# telfer-control.net
KiCad netlist of a schematic drawn in EAGLE
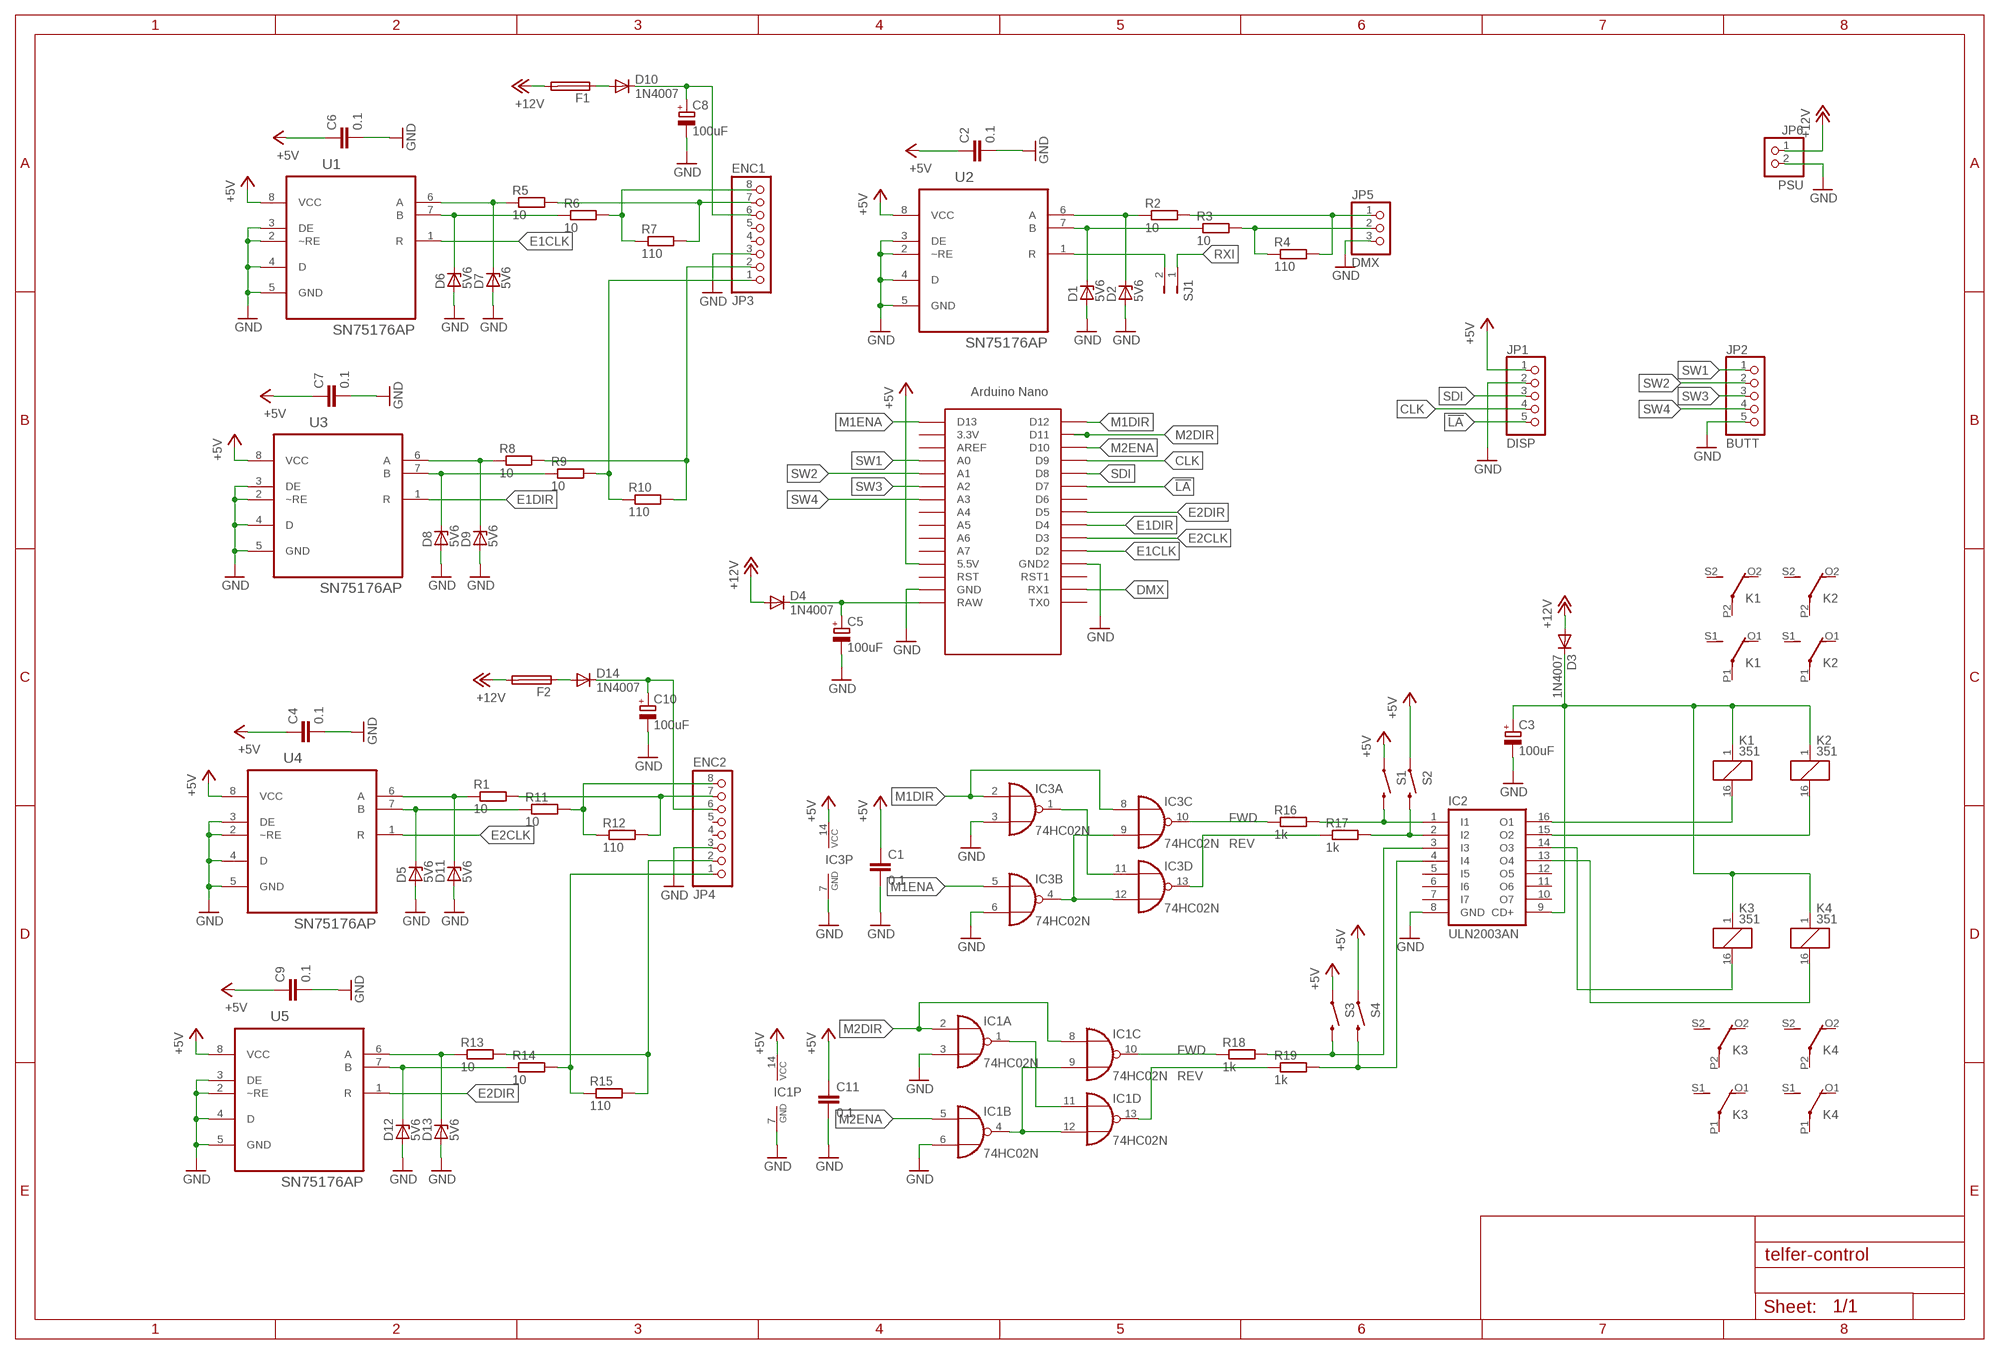
[diagram p0: schematic, sheet 1]

(export (version "E")
  (design (tool "Eeschema 10.0.6"))
  (components
    (comp (ref "C1")
      (value "0.1")
      (footprint "eagle-import:C050-025X075")
      (libsource (lib "eagle-import") (part "C-EU050-025X075"))
    )
    (comp (ref "C2")
      (value "0.1")
      (footprint "eagle-import:C050-025X075")
      (libsource (lib "eagle-import") (part "C-EU050-025X075"))
    )
    (comp (ref "C3")
      (value "100uF")
      (footprint "eagle-import:E2,5-7")
      (libsource (lib "eagle-import") (part "CPOL-EUE2.5-7"))
    )
    (comp (ref "C4")
      (value "0.1")
      (footprint "eagle-import:C050-025X075")
      (libsource (lib "eagle-import") (part "C-EU050-025X075"))
    )
    (comp (ref "C5")
      (value "100uF")
      (footprint "eagle-import:E2,5-7")
      (libsource (lib "eagle-import") (part "CPOL-EUE2.5-7"))
    )
    (comp (ref "C6")
      (value "0.1")
      (footprint "eagle-import:C050-025X075")
      (libsource (lib "eagle-import") (part "C-EU050-025X075"))
    )
    (comp (ref "C7")
      (value "0.1")
      (footprint "eagle-import:C050-025X075")
      (libsource (lib "eagle-import") (part "C-EU050-025X075"))
    )
    (comp (ref "C8")
      (value "100uF")
      (footprint "eagle-import:E2,5-7")
      (libsource (lib "eagle-import") (part "CPOL-EUE2.5-7"))
    )
    (comp (ref "C9")
      (value "0.1")
      (footprint "eagle-import:C050-025X075")
      (libsource (lib "eagle-import") (part "C-EU050-025X075"))
    )
    (comp (ref "C10")
      (value "100uF")
      (footprint "eagle-import:E2,5-7")
      (libsource (lib "eagle-import") (part "CPOL-EUE2.5-7"))
    )
    (comp (ref "C11")
      (value "0.1")
      (footprint "eagle-import:C050-025X075")
      (libsource (lib "eagle-import") (part "C-EU050-025X075"))
    )
    (comp (ref "D1")
      (value "5V6")
      (footprint "eagle-import:DO34Z7")
      (libsource (lib "eagle-import") (part "ZENER-DIODEDO34-7"))
    )
    (comp (ref "D2")
      (value "5V6")
      (footprint "eagle-import:DO34Z7")
      (libsource (lib "eagle-import") (part "ZENER-DIODEDO34-7"))
    )
    (comp (ref "D3")
      (value "1N4007")
      (footprint "eagle-import:DO41-10")
      (libsource (lib "eagle-import") (part "DIODE-DO41-10"))
    )
    (comp (ref "D4")
      (value "1N4007")
      (footprint "eagle-import:DO41-10")
      (libsource (lib "eagle-import") (part "DIODE-DO41-10"))
    )
    (comp (ref "D5")
      (value "5V6")
      (footprint "eagle-import:DO34Z7")
      (libsource (lib "eagle-import") (part "ZENER-DIODEDO34-7"))
    )
    (comp (ref "D6")
      (value "5V6")
      (footprint "eagle-import:DO34Z7")
      (libsource (lib "eagle-import") (part "ZENER-DIODEDO34-7"))
    )
    (comp (ref "D7")
      (value "5V6")
      (footprint "eagle-import:DO34Z7")
      (libsource (lib "eagle-import") (part "ZENER-DIODEDO34-7"))
    )
    (comp (ref "D8")
      (value "5V6")
      (footprint "eagle-import:DO34Z7")
      (libsource (lib "eagle-import") (part "ZENER-DIODEDO34-7"))
    )
    (comp (ref "D9")
      (value "5V6")
      (footprint "eagle-import:DO34Z7")
      (libsource (lib "eagle-import") (part "ZENER-DIODEDO34-7"))
    )
    (comp (ref "D10")
      (value "1N4007")
      (footprint "eagle-import:DO41-10")
      (libsource (lib "eagle-import") (part "DIODE-DO41-10"))
    )
    (comp (ref "D11")
      (value "5V6")
      (footprint "eagle-import:DO34Z7")
      (libsource (lib "eagle-import") (part "ZENER-DIODEDO34-7"))
    )
    (comp (ref "D12")
      (value "5V6")
      (footprint "eagle-import:DO34Z7")
      (libsource (lib "eagle-import") (part "ZENER-DIODEDO34-7"))
    )
    (comp (ref "D13")
      (value "5V6")
      (footprint "eagle-import:DO34Z7")
      (libsource (lib "eagle-import") (part "ZENER-DIODEDO34-7"))
    )
    (comp (ref "D14")
      (value "1N4007")
      (footprint "eagle-import:DO41-10")
      (libsource (lib "eagle-import") (part "DIODE-DO41-10"))
    )
    (comp (ref "F1")
      (value "PICOFUSE")
      (footprint "eagle-import:PICOFUSE")
      (libsource (lib "eagle-import") (part "PICOFUSE"))
    )
    (comp (ref "F2")
      (value "PICOFUSE")
      (footprint "eagle-import:PICOFUSE")
      (libsource (lib "eagle-import") (part "PICOFUSE"))
    )
    (comp (ref "IC1")
      (value "74HC02N")
      (footprint "eagle-import:DIL14")
      (libsource (lib "eagle-import") (part "7402NHC"))
    )
    (comp (ref "IC2")
      (value "ULN2003AN")
      (footprint "eagle-import:DIL16")
      (libsource (lib "eagle-import") (part "ULN2003AN"))
    )
    (comp (ref "IC3")
      (value "74HC02N")
      (footprint "eagle-import:DIL14")
      (libsource (lib "eagle-import") (part "7402NHC"))
    )
    (comp (ref "JP1")
      (value "DISP")
      (footprint "eagle-import:1X05")
      (libsource (lib "eagle-import") (part "PINHD-1X5"))
    )
    (comp (ref "JP2")
      (value "BUTT")
      (footprint "eagle-import:1X05")
      (libsource (lib "eagle-import") (part "PINHD-1X5"))
    )
    (comp (ref "JP3")
      (value "ENC1")
      (footprint "eagle-import:1X08")
      (libsource (lib "eagle-import") (part "PINHD-1X8"))
    )
    (comp (ref "JP4")
      (value "ENC2")
      (footprint "eagle-import:1X08")
      (libsource (lib "eagle-import") (part "PINHD-1X8"))
    )
    (comp (ref "JP5")
      (value "DMX")
      (footprint "eagle-import:1X03")
      (libsource (lib "eagle-import") (part "PINHD-1X3"))
    )
    (comp (ref "JP6")
      (value "PSU")
      (footprint "eagle-import:1X02")
      (libsource (lib "eagle-import") (part "PINHD-1X2"))
    )
    (comp (ref "K1")
      (value "351")
      (footprint "eagle-import:351")
      (libsource (lib "eagle-import") (part "351"))
    )
    (comp (ref "K2")
      (value "351")
      (footprint "eagle-import:351")
      (libsource (lib "eagle-import") (part "351"))
    )
    (comp (ref "K3")
      (value "351")
      (footprint "eagle-import:351")
      (libsource (lib "eagle-import") (part "351"))
    )
    (comp (ref "K4")
      (value "351")
      (footprint "eagle-import:351")
      (libsource (lib "eagle-import") (part "351"))
    )
    (comp (ref "R1")
      (value "10")
      (footprint "eagle-import:0204_7")
      (libsource (lib "eagle-import") (part "R-EU_0204/7"))
    )
    (comp (ref "R2")
      (value "10")
      (footprint "eagle-import:0204_7")
      (libsource (lib "eagle-import") (part "R-EU_0204/7"))
    )
    (comp (ref "R3")
      (value "10")
      (footprint "eagle-import:0204_7")
      (libsource (lib "eagle-import") (part "R-EU_0204/7"))
    )
    (comp (ref "R4")
      (value "110")
      (footprint "eagle-import:0204_7")
      (libsource (lib "eagle-import") (part "R-EU_0204/7"))
    )
    (comp (ref "R5")
      (value "10")
      (footprint "eagle-import:0204_7")
      (libsource (lib "eagle-import") (part "R-EU_0204/7"))
    )
    (comp (ref "R6")
      (value "10")
      (footprint "eagle-import:0204_7")
      (libsource (lib "eagle-import") (part "R-EU_0204/7"))
    )
    (comp (ref "R7")
      (value "110")
      (footprint "eagle-import:0204_7")
      (libsource (lib "eagle-import") (part "R-EU_0204/7"))
    )
    (comp (ref "R8")
      (value "10")
      (footprint "eagle-import:0204_7")
      (libsource (lib "eagle-import") (part "R-EU_0204/7"))
    )
    (comp (ref "R9")
      (value "10")
      (footprint "eagle-import:0204_7")
      (libsource (lib "eagle-import") (part "R-EU_0204/7"))
    )
    (comp (ref "R10")
      (value "110")
      (footprint "eagle-import:0204_7")
      (libsource (lib "eagle-import") (part "R-EU_0204/7"))
    )
    (comp (ref "R11")
      (value "10")
      (footprint "eagle-import:0204_7")
      (libsource (lib "eagle-import") (part "R-EU_0204/7"))
    )
    (comp (ref "R12")
      (value "110")
      (footprint "eagle-import:0204_7")
      (libsource (lib "eagle-import") (part "R-EU_0204/7"))
    )
    (comp (ref "R13")
      (value "10")
      (footprint "eagle-import:0204_7")
      (libsource (lib "eagle-import") (part "R-EU_0204/7"))
    )
    (comp (ref "R14")
      (value "10")
      (footprint "eagle-import:0204_7")
      (libsource (lib "eagle-import") (part "R-EU_0204/7"))
    )
    (comp (ref "R15")
      (value "110")
      (footprint "eagle-import:0204_7")
      (libsource (lib "eagle-import") (part "R-EU_0204/7"))
    )
    (comp (ref "R16")
      (value "1k")
      (footprint "eagle-import:0204_7")
      (libsource (lib "eagle-import") (part "R-EU_0204/7"))
    )
    (comp (ref "R17")
      (value "1k")
      (footprint "eagle-import:0204_7")
      (libsource (lib "eagle-import") (part "R-EU_0204/7"))
    )
    (comp (ref "R18")
      (value "1k")
      (footprint "eagle-import:0204_7")
      (libsource (lib "eagle-import") (part "R-EU_0204/7"))
    )
    (comp (ref "R19")
      (value "1k")
      (footprint "eagle-import:0204_7")
      (libsource (lib "eagle-import") (part "R-EU_0204/7"))
    )
    (comp (ref "S1")
      (value "SWITCH-MOMENTARY-2PTH")
      (footprint "eagle-import:TACTILE-PTH")
      (libsource (lib "eagle-import") (part "SWITCH-MOMENTARY-2PTH"))
    )
    (comp (ref "S2")
      (value "SWITCH-MOMENTARY-2PTH")
      (footprint "eagle-import:TACTILE-PTH")
      (libsource (lib "eagle-import") (part "SWITCH-MOMENTARY-2PTH"))
    )
    (comp (ref "S3")
      (value "SWITCH-MOMENTARY-2PTH")
      (footprint "eagle-import:TACTILE-PTH")
      (libsource (lib "eagle-import") (part "SWITCH-MOMENTARY-2PTH"))
    )
    (comp (ref "S4")
      (value "SWITCH-MOMENTARY-2PTH")
      (footprint "eagle-import:TACTILE-PTH")
      (libsource (lib "eagle-import") (part "SWITCH-MOMENTARY-2PTH"))
    )
    (comp (ref "SJ1")
      (value "JUMPER-PTH-2-NO")
      (footprint "eagle-import:PTH-JUMPER-2-NO_NO_SILK")
      (libsource (lib "eagle-import") (part "JUMPER-PTH-2-NO"))
    )
    (comp (ref "U$1")
      (value "NANO")
      (footprint "eagle-import:NANO")
      (libsource (lib "eagle-import") (part "NANO"))
    )
    (comp (ref "U1")
      (value "SN75176AP")
      (footprint "eagle-import:DIP254P762X508-8")
      (libsource (lib "eagle-import") (part "SN75176AP"))
    )
    (comp (ref "U2")
      (value "SN75176AP")
      (footprint "eagle-import:DIP254P762X508-8")
      (libsource (lib "eagle-import") (part "SN75176AP"))
    )
    (comp (ref "U3")
      (value "SN75176AP")
      (footprint "eagle-import:DIP254P762X508-8")
      (libsource (lib "eagle-import") (part "SN75176AP"))
    )
    (comp (ref "U4")
      (value "SN75176AP")
      (footprint "eagle-import:DIP254P762X508-8")
      (libsource (lib "eagle-import") (part "SN75176AP"))
    )
    (comp (ref "U5")
      (value "SN75176AP")
      (footprint "eagle-import:DIP254P762X508-8")
      (libsource (lib "eagle-import") (part "SN75176AP"))
    )
  )
  (nets
    (net (code "1") (name "+5V") (class "Default")
      (node (ref "C1") (pin "1") (pinfunction "1_1") (pintype "passive"))
      (node (ref "C11") (pin "1") (pinfunction "1_1") (pintype "passive"))
      (node (ref "C2") (pin "1") (pinfunction "1_1") (pintype "passive"))
      (node (ref "C4") (pin "1") (pinfunction "1_1") (pintype "passive"))
      (node (ref "C6") (pin "1") (pinfunction "1_1") (pintype "passive"))
      (node (ref "C7") (pin "1") (pinfunction "1_1") (pintype "passive"))
      (node (ref "C9") (pin "1") (pinfunction "1_1") (pintype "passive"))
      (node (ref "IC1") (pin "14") (pinfunction "VCC_14") (pintype "power_in"))
      (node (ref "IC3") (pin "14") (pinfunction "VCC_14") (pintype "power_in"))
      (node (ref "JP1") (pin "1") (pinfunction "1_1") (pintype "passive"))
      (node (ref "S1") (pin "1") (pinfunction "1_1") (pintype "passive"))
      (node (ref "S2") (pin "1") (pinfunction "1_1") (pintype "passive"))
      (node (ref "S3") (pin "1") (pinfunction "1_1") (pintype "passive"))
      (node (ref "S4") (pin "1") (pinfunction "1_1") (pintype "passive"))
      (node (ref "U$1") (pin "5V") (pinfunction "5.5V_5V") (pintype "bidirectional"))
      (node (ref "U1") (pin "8") (pinfunction "VCC_8") (pintype "power_in"))
      (node (ref "U2") (pin "8") (pinfunction "VCC_8") (pintype "power_in"))
      (node (ref "U3") (pin "8") (pinfunction "VCC_8") (pintype "power_in"))
      (node (ref "U4") (pin "8") (pinfunction "VCC_8") (pintype "power_in"))
      (node (ref "U5") (pin "8") (pinfunction "VCC_8") (pintype "power_in"))
    )
    (net (code "2") (name "+12V") (class "Default")
      (node (ref "D3") (pin "A") (pinfunction "A_A") (pintype "passive"))
      (node (ref "D4") (pin "A") (pinfunction "A_A") (pintype "passive"))
      (node (ref "F1") (pin "2") (pinfunction "2_2") (pintype "passive"))
      (node (ref "F2") (pin "2") (pinfunction "2_2") (pintype "passive"))
      (node (ref "JP6") (pin "1") (pinfunction "1_1") (pintype "passive"))
    )
    (net (code "3") (name "/FWD") (class "Default")
      (node (ref "IC1") (pin "10") (pinfunction "O_10") (pintype "output"))
      (node (ref "IC3") (pin "10") (pinfunction "O_10") (pintype "output"))
      (node (ref "R16") (pin "1") (pinfunction "1_1") (pintype "passive"))
      (node (ref "R18") (pin "1") (pinfunction "1_1") (pintype "passive"))
    )
    (net (code "4") (name "/REV") (class "Default")
      (node (ref "IC1") (pin "13") (pinfunction "O_13") (pintype "output"))
      (node (ref "IC3") (pin "13") (pinfunction "O_13") (pintype "output"))
      (node (ref "R17") (pin "1") (pinfunction "1_1") (pintype "passive"))
      (node (ref "R19") (pin "1") (pinfunction "1_1") (pintype "passive"))
    )
    (net (code "5") (name "/~{LA}") (class "Default")
      (node (ref "JP1") (pin "5") (pinfunction "5_5") (pintype "passive"))
      (node (ref "U$1") (pin "D7") (pinfunction "D7_D7") (pintype "bidirectional"))
    )
    (net (code "6") (name "CLK") (class "Default")
      (node (ref "JP1") (pin "4") (pinfunction "4_4") (pintype "passive"))
      (node (ref "U$1") (pin "D9") (pinfunction "D9_D9") (pintype "bidirectional"))
    )
    (net (code "7") (name "DMX") (class "Default")
      (node (ref "U$1") (pin "RX1") (pinfunction "RX1_RX1") (pintype "bidirectional"))
    )
    (net (code "8") (name "E1CLK") (class "Default")
      (node (ref "U$1") (pin "D2") (pinfunction "D2_D2") (pintype "bidirectional"))
      (node (ref "U1") (pin "1") (pinfunction "R_1") (pintype "output"))
    )
    (net (code "9") (name "E1DIR") (class "Default")
      (node (ref "U$1") (pin "D4") (pinfunction "D4_D4") (pintype "bidirectional"))
      (node (ref "U3") (pin "1") (pinfunction "R_1") (pintype "output"))
    )
    (net (code "10") (name "E2CLK") (class "Default")
      (node (ref "U$1") (pin "D3") (pinfunction "D3_D3") (pintype "bidirectional"))
      (node (ref "U4") (pin "1") (pinfunction "R_1") (pintype "output"))
    )
    (net (code "11") (name "E2DIR") (class "Default")
      (node (ref "U$1") (pin "D5") (pinfunction "D5_D5") (pintype "bidirectional"))
      (node (ref "U5") (pin "1") (pinfunction "R_1") (pintype "output"))
    )
    (net (code "12") (name "GND") (class "Default")
      (node (ref "C1") (pin "2") (pinfunction "2_2") (pintype "passive"))
      (node (ref "C10") (pin "-") (pinfunction "-_-") (pintype "passive"))
      (node (ref "C11") (pin "2") (pinfunction "2_2") (pintype "passive"))
      (node (ref "C2") (pin "2") (pinfunction "2_2") (pintype "passive"))
      (node (ref "C3") (pin "-") (pinfunction "-_-") (pintype "passive"))
      (node (ref "C4") (pin "2") (pinfunction "2_2") (pintype "passive"))
      (node (ref "C5") (pin "-") (pinfunction "-_-") (pintype "passive"))
      (node (ref "C6") (pin "2") (pinfunction "2_2") (pintype "passive"))
      (node (ref "C7") (pin "2") (pinfunction "2_2") (pintype "passive"))
      (node (ref "C8") (pin "-") (pinfunction "-_-") (pintype "passive"))
      (node (ref "C9") (pin "2") (pinfunction "2_2") (pintype "passive"))
      (node (ref "D1") (pin "A") (pinfunction "A_A") (pintype "passive"))
      (node (ref "D11") (pin "A") (pinfunction "A_A") (pintype "passive"))
      (node (ref "D12") (pin "A") (pinfunction "A_A") (pintype "passive"))
      (node (ref "D13") (pin "A") (pinfunction "A_A") (pintype "passive"))
      (node (ref "D2") (pin "A") (pinfunction "A_A") (pintype "passive"))
      (node (ref "D5") (pin "A") (pinfunction "A_A") (pintype "passive"))
      (node (ref "D6") (pin "A") (pinfunction "A_A") (pintype "passive"))
      (node (ref "D7") (pin "A") (pinfunction "A_A") (pintype "passive"))
      (node (ref "D8") (pin "A") (pinfunction "A_A") (pintype "passive"))
      (node (ref "D9") (pin "A") (pinfunction "A_A") (pintype "passive"))
      (node (ref "IC1") (pin "3") (pinfunction "I1_3") (pintype "input"))
      (node (ref "IC1") (pin "6") (pinfunction "I1_6") (pintype "input"))
      (node (ref "IC1") (pin "7") (pinfunction "GND_7") (pintype "power_in"))
      (node (ref "IC2") (pin "8") (pinfunction "GND_8") (pintype "power_in"))
      (node (ref "IC3") (pin "3") (pinfunction "I1_3") (pintype "input"))
      (node (ref "IC3") (pin "6") (pinfunction "I1_6") (pintype "input"))
      (node (ref "IC3") (pin "7") (pinfunction "GND_7") (pintype "power_in"))
      (node (ref "JP1") (pin "2") (pinfunction "2_2") (pintype "passive"))
      (node (ref "JP2") (pin "5") (pinfunction "5_5") (pintype "passive"))
      (node (ref "JP3") (pin "3") (pinfunction "3_3") (pintype "passive"))
      (node (ref "JP4") (pin "3") (pinfunction "3_3") (pintype "passive"))
      (node (ref "JP5") (pin "3") (pinfunction "3_3") (pintype "passive"))
      (node (ref "JP6") (pin "2") (pinfunction "2_2") (pintype "passive"))
      (node (ref "U$1") (pin "GND") (pinfunction "GND_GND") (pintype "bidirectional"))
      (node (ref "U$1") (pin "GND1") (pinfunction "GND2_GND1") (pintype "bidirectional"))
      (node (ref "U1") (pin "2") (pinfunction "~{RE}_2") (pintype "input"))
      (node (ref "U1") (pin "3") (pinfunction "DE_3") (pintype "input"))
      (node (ref "U1") (pin "4") (pinfunction "D_4") (pintype "input"))
      (node (ref "U1") (pin "5") (pinfunction "GND_5") (pintype "passive"))
      (node (ref "U2") (pin "2") (pinfunction "~{RE}_2") (pintype "input"))
      (node (ref "U2") (pin "3") (pinfunction "DE_3") (pintype "input"))
      (node (ref "U2") (pin "4") (pinfunction "D_4") (pintype "input"))
      (node (ref "U2") (pin "5") (pinfunction "GND_5") (pintype "passive"))
      (node (ref "U3") (pin "2") (pinfunction "~{RE}_2") (pintype "input"))
      (node (ref "U3") (pin "3") (pinfunction "DE_3") (pintype "input"))
      (node (ref "U3") (pin "4") (pinfunction "D_4") (pintype "input"))
      (node (ref "U3") (pin "5") (pinfunction "GND_5") (pintype "passive"))
      (node (ref "U4") (pin "2") (pinfunction "~{RE}_2") (pintype "input"))
      (node (ref "U4") (pin "3") (pinfunction "DE_3") (pintype "input"))
      (node (ref "U4") (pin "4") (pinfunction "D_4") (pintype "input"))
      (node (ref "U4") (pin "5") (pinfunction "GND_5") (pintype "passive"))
      (node (ref "U5") (pin "2") (pinfunction "~{RE}_2") (pintype "input"))
      (node (ref "U5") (pin "3") (pinfunction "DE_3") (pintype "input"))
      (node (ref "U5") (pin "4") (pinfunction "D_4") (pintype "input"))
      (node (ref "U5") (pin "5") (pinfunction "GND_5") (pintype "passive"))
    )
    (net (code "13") (name "M1DIR") (class "Default")
      (node (ref "IC3") (pin "2") (pinfunction "I0_2") (pintype "input"))
      (node (ref "IC3") (pin "8") (pinfunction "I0_8") (pintype "input"))
      (node (ref "U$1") (pin "D12") (pinfunction "D12_D12") (pintype "bidirectional"))
    )
    (net (code "14") (name "M1ENA") (class "Default")
      (node (ref "IC3") (pin "5") (pinfunction "I0_5") (pintype "input"))
      (node (ref "U$1") (pin "D13") (pinfunction "D13_D13") (pintype "bidirectional"))
    )
    (net (code "15") (name "M2DIR") (class "Default")
      (node (ref "IC1") (pin "2") (pinfunction "I0_2") (pintype "input"))
      (node (ref "IC1") (pin "8") (pinfunction "I0_8") (pintype "input"))
      (node (ref "U$1") (pin "D11") (pinfunction "D11_D11") (pintype "bidirectional"))
    )
    (net (code "16") (name "M2ENA") (class "Default")
      (node (ref "IC1") (pin "5") (pinfunction "I0_5") (pintype "input"))
      (node (ref "U$1") (pin "D10") (pinfunction "D10_D10") (pintype "bidirectional"))
    )
    (net (code "17") (name "Net-(C5-Pad+)") (class "Default")
      (node (ref "C5") (pin "+") (pinfunction "+_+") (pintype "passive"))
      (node (ref "D4") (pin "C") (pinfunction "C_C") (pintype "passive"))
      (node (ref "U$1") (pin "RAW") (pinfunction "RAW_RAW") (pintype "bidirectional"))
    )
    (net (code "18") (name "Net-(C8-Pad+)") (class "Default")
      (node (ref "C8") (pin "+") (pinfunction "+_+") (pintype "passive"))
      (node (ref "D10") (pin "C") (pinfunction "C_C") (pintype "passive"))
      (node (ref "JP3") (pin "6") (pinfunction "6_6") (pintype "passive"))
    )
    (net (code "19") (name "Net-(C10-Pad+)") (class "Default")
      (node (ref "C10") (pin "+") (pinfunction "+_+") (pintype "passive"))
      (node (ref "D14") (pin "C") (pinfunction "C_C") (pintype "passive"))
      (node (ref "JP4") (pin "6") (pinfunction "6_6") (pintype "passive"))
    )
    (net (code "20") (name "Net-(D10-PadA)") (class "Default")
      (node (ref "D10") (pin "A") (pinfunction "A_A") (pintype "passive"))
      (node (ref "F1") (pin "1") (pinfunction "1_1") (pintype "passive"))
    )
    (net (code "21") (name "Net-(D14-PadA)") (class "Default")
      (node (ref "D14") (pin "A") (pinfunction "A_A") (pintype "passive"))
      (node (ref "F2") (pin "1") (pinfunction "1_1") (pintype "passive"))
    )
    (net (code "22") (name "Net-(IC1A-O)") (class "Default")
      (node (ref "IC1") (pin "1") (pinfunction "O_1") (pintype "output"))
      (node (ref "IC1") (pin "11") (pinfunction "I0_11") (pintype "input"))
    )
    (net (code "23") (name "Net-(IC1B-O)") (class "Default")
      (node (ref "IC1") (pin "12") (pinfunction "I1_12") (pintype "input"))
      (node (ref "IC1") (pin "4") (pinfunction "O_4") (pintype "output"))
      (node (ref "IC1") (pin "9") (pinfunction "I1_9") (pintype "input"))
    )
    (net (code "24") (name "Net-(IC2-CD+)") (class "Default")
      (node (ref "C3") (pin "+") (pinfunction "+_+") (pintype "passive"))
      (node (ref "D3") (pin "C") (pinfunction "C_C") (pintype "passive"))
      (node (ref "IC2") (pin "9") (pinfunction "CD+_9") (pintype "passive"))
      (node (ref "K1") (pin "1") (pinfunction "1_1") (pintype "passive"))
      (node (ref "K2") (pin "1") (pinfunction "1_1") (pintype "passive"))
      (node (ref "K3") (pin "1") (pinfunction "1_1") (pintype "passive"))
      (node (ref "K4") (pin "1") (pinfunction "1_1") (pintype "passive"))
    )
    (net (code "25") (name "Net-(IC2-I1)") (class "Default")
      (node (ref "IC2") (pin "1") (pinfunction "I1_1") (pintype "input"))
      (node (ref "R16") (pin "2") (pinfunction "2_2") (pintype "passive"))
      (node (ref "S1") (pin "3") (pinfunction "2_3") (pintype "passive"))
    )
    (net (code "26") (name "Net-(IC2-I2)") (class "Default")
      (node (ref "IC2") (pin "2") (pinfunction "I2_2") (pintype "input"))
      (node (ref "R17") (pin "2") (pinfunction "2_2") (pintype "passive"))
      (node (ref "S2") (pin "3") (pinfunction "2_3") (pintype "passive"))
    )
    (net (code "27") (name "Net-(IC2-I3)") (class "Default")
      (node (ref "IC2") (pin "3") (pinfunction "I3_3") (pintype "input"))
      (node (ref "R18") (pin "2") (pinfunction "2_2") (pintype "passive"))
      (node (ref "S3") (pin "3") (pinfunction "2_3") (pintype "passive"))
    )
    (net (code "28") (name "Net-(IC2-I4)") (class "Default")
      (node (ref "IC2") (pin "4") (pinfunction "I4_4") (pintype "input"))
      (node (ref "R19") (pin "2") (pinfunction "2_2") (pintype "passive"))
      (node (ref "S4") (pin "3") (pinfunction "2_3") (pintype "passive"))
    )
    (net (code "29") (name "Net-(IC2-O1)") (class "Default")
      (node (ref "IC2") (pin "16") (pinfunction "O1_16") (pintype "open_collector"))
      (node (ref "K1") (pin "16") (pinfunction "2_16") (pintype "passive"))
    )
    (net (code "30") (name "Net-(IC2-O2)") (class "Default")
      (node (ref "IC2") (pin "15") (pinfunction "O2_15") (pintype "open_collector"))
      (node (ref "K2") (pin "16") (pinfunction "2_16") (pintype "passive"))
    )
    (net (code "31") (name "Net-(IC2-O3)") (class "Default")
      (node (ref "IC2") (pin "14") (pinfunction "O3_14") (pintype "open_collector"))
      (node (ref "K3") (pin "16") (pinfunction "2_16") (pintype "passive"))
    )
    (net (code "32") (name "Net-(IC2-O4)") (class "Default")
      (node (ref "IC2") (pin "13") (pinfunction "O4_13") (pintype "open_collector"))
      (node (ref "K4") (pin "16") (pinfunction "2_16") (pintype "passive"))
    )
    (net (code "33") (name "Net-(IC3A-O)") (class "Default")
      (node (ref "IC3") (pin "1") (pinfunction "O_1") (pintype "output"))
      (node (ref "IC3") (pin "11") (pinfunction "I0_11") (pintype "input"))
    )
    (net (code "34") (name "Net-(IC3B-O)") (class "Default")
      (node (ref "IC3") (pin "12") (pinfunction "I1_12") (pintype "input"))
      (node (ref "IC3") (pin "4") (pinfunction "O_4") (pintype "output"))
      (node (ref "IC3") (pin "9") (pinfunction "I1_9") (pintype "input"))
    )
    (net (code "35") (name "Net-(JP3-Pad1)") (class "Default")
      (node (ref "JP3") (pin "1") (pinfunction "1_1") (pintype "passive"))
      (node (ref "R10") (pin "1") (pinfunction "1_1") (pintype "passive"))
      (node (ref "R9") (pin "2") (pinfunction "2_2") (pintype "passive"))
    )
    (net (code "36") (name "Net-(JP3-Pad2)") (class "Default")
      (node (ref "JP3") (pin "2") (pinfunction "2_2") (pintype "passive"))
      (node (ref "R10") (pin "2") (pinfunction "2_2") (pintype "passive"))
      (node (ref "R8") (pin "2") (pinfunction "2_2") (pintype "passive"))
    )
    (net (code "37") (name "Net-(JP3-Pad7)") (class "Default")
      (node (ref "JP3") (pin "7") (pinfunction "7_7") (pintype "passive"))
      (node (ref "R5") (pin "2") (pinfunction "2_2") (pintype "passive"))
      (node (ref "R7") (pin "2") (pinfunction "2_2") (pintype "passive"))
    )
    (net (code "38") (name "Net-(JP3-Pad8)") (class "Default")
      (node (ref "JP3") (pin "8") (pinfunction "8_8") (pintype "passive"))
      (node (ref "R6") (pin "2") (pinfunction "2_2") (pintype "passive"))
      (node (ref "R7") (pin "1") (pinfunction "1_1") (pintype "passive"))
    )
    (net (code "39") (name "Net-(JP4-Pad1)") (class "Default")
      (node (ref "JP4") (pin "1") (pinfunction "1_1") (pintype "passive"))
      (node (ref "R14") (pin "2") (pinfunction "2_2") (pintype "passive"))
      (node (ref "R15") (pin "1") (pinfunction "1_1") (pintype "passive"))
    )
    (net (code "40") (name "Net-(JP4-Pad2)") (class "Default")
      (node (ref "JP4") (pin "2") (pinfunction "2_2") (pintype "passive"))
      (node (ref "R13") (pin "2") (pinfunction "2_2") (pintype "passive"))
      (node (ref "R15") (pin "2") (pinfunction "2_2") (pintype "passive"))
    )
    (net (code "41") (name "Net-(JP4-Pad7)") (class "Default")
      (node (ref "JP4") (pin "7") (pinfunction "7_7") (pintype "passive"))
      (node (ref "R1") (pin "2") (pinfunction "2_2") (pintype "passive"))
      (node (ref "R12") (pin "2") (pinfunction "2_2") (pintype "passive"))
    )
    (net (code "42") (name "Net-(JP4-Pad8)") (class "Default")
      (node (ref "JP4") (pin "8") (pinfunction "8_8") (pintype "passive"))
      (node (ref "R11") (pin "2") (pinfunction "2_2") (pintype "passive"))
      (node (ref "R12") (pin "1") (pinfunction "1_1") (pintype "passive"))
    )
    (net (code "43") (name "Net-(JP5-Pad1)") (class "Default")
      (node (ref "JP5") (pin "1") (pinfunction "1_1") (pintype "passive"))
      (node (ref "R2") (pin "2") (pinfunction "2_2") (pintype "passive"))
      (node (ref "R4") (pin "2") (pinfunction "2_2") (pintype "passive"))
    )
    (net (code "44") (name "Net-(JP5-Pad2)") (class "Default")
      (node (ref "JP5") (pin "2") (pinfunction "2_2") (pintype "passive"))
      (node (ref "R3") (pin "2") (pinfunction "2_2") (pintype "passive"))
      (node (ref "R4") (pin "1") (pinfunction "1_1") (pintype "passive"))
    )
    (net (code "45") (name "Net-(U1-A)") (class "Default")
      (node (ref "D7") (pin "C") (pinfunction "C_C") (pintype "passive"))
      (node (ref "R5") (pin "1") (pinfunction "1_1") (pintype "passive"))
      (node (ref "U1") (pin "6") (pinfunction "A_6") (pintype "bidirectional"))
    )
    (net (code "46") (name "Net-(U1-B)") (class "Default")
      (node (ref "D6") (pin "C") (pinfunction "C_C") (pintype "passive"))
      (node (ref "R6") (pin "1") (pinfunction "1_1") (pintype "passive"))
      (node (ref "U1") (pin "7") (pinfunction "B_7") (pintype "bidirectional"))
    )
    (net (code "47") (name "Net-(U2-A)") (class "Default")
      (node (ref "D2") (pin "C") (pinfunction "C_C") (pintype "passive"))
      (node (ref "R2") (pin "1") (pinfunction "1_1") (pintype "passive"))
      (node (ref "U2") (pin "6") (pinfunction "A_6") (pintype "bidirectional"))
    )
    (net (code "48") (name "Net-(U2-B)") (class "Default")
      (node (ref "D1") (pin "C") (pinfunction "C_C") (pintype "passive"))
      (node (ref "R3") (pin "1") (pinfunction "1_1") (pintype "passive"))
      (node (ref "U2") (pin "7") (pinfunction "B_7") (pintype "bidirectional"))
    )
    (net (code "49") (name "Net-(U2-R)") (class "Default")
      (node (ref "SJ1") (pin "2") (pinfunction "2_2") (pintype "passive"))
      (node (ref "U2") (pin "1") (pinfunction "R_1") (pintype "output"))
    )
    (net (code "50") (name "Net-(U3-A)") (class "Default")
      (node (ref "D9") (pin "C") (pinfunction "C_C") (pintype "passive"))
      (node (ref "R8") (pin "1") (pinfunction "1_1") (pintype "passive"))
      (node (ref "U3") (pin "6") (pinfunction "A_6") (pintype "bidirectional"))
    )
    (net (code "51") (name "Net-(U3-B)") (class "Default")
      (node (ref "D8") (pin "C") (pinfunction "C_C") (pintype "passive"))
      (node (ref "R9") (pin "1") (pinfunction "1_1") (pintype "passive"))
      (node (ref "U3") (pin "7") (pinfunction "B_7") (pintype "bidirectional"))
    )
    (net (code "52") (name "Net-(U4-A)") (class "Default")
      (node (ref "D11") (pin "C") (pinfunction "C_C") (pintype "passive"))
      (node (ref "R1") (pin "1") (pinfunction "1_1") (pintype "passive"))
      (node (ref "U4") (pin "6") (pinfunction "A_6") (pintype "bidirectional"))
    )
    (net (code "53") (name "Net-(U4-B)") (class "Default")
      (node (ref "D5") (pin "C") (pinfunction "C_C") (pintype "passive"))
      (node (ref "R11") (pin "1") (pinfunction "1_1") (pintype "passive"))
      (node (ref "U4") (pin "7") (pinfunction "B_7") (pintype "bidirectional"))
    )
    (net (code "54") (name "Net-(U5-A)") (class "Default")
      (node (ref "D13") (pin "C") (pinfunction "C_C") (pintype "passive"))
      (node (ref "R13") (pin "1") (pinfunction "1_1") (pintype "passive"))
      (node (ref "U5") (pin "6") (pinfunction "A_6") (pintype "bidirectional"))
    )
    (net (code "55") (name "Net-(U5-B)") (class "Default")
      (node (ref "D12") (pin "C") (pinfunction "C_C") (pintype "passive"))
      (node (ref "R14") (pin "1") (pinfunction "1_1") (pintype "passive"))
      (node (ref "U5") (pin "7") (pinfunction "B_7") (pintype "bidirectional"))
    )
    (net (code "56") (name "RXI") (class "Default")
      (node (ref "SJ1") (pin "1") (pinfunction "1_1") (pintype "passive"))
    )
    (net (code "57") (name "SDI") (class "Default")
      (node (ref "JP1") (pin "3") (pinfunction "3_3") (pintype "passive"))
      (node (ref "U$1") (pin "D8") (pinfunction "D8_D8") (pintype "bidirectional"))
    )
    (net (code "58") (name "SW1") (class "Default")
      (node (ref "JP2") (pin "1") (pinfunction "1_1") (pintype "passive"))
      (node (ref "U$1") (pin "A0") (pinfunction "A0_A0") (pintype "bidirectional"))
    )
    (net (code "59") (name "SW2") (class "Default")
      (node (ref "JP2") (pin "2") (pinfunction "2_2") (pintype "passive"))
      (node (ref "U$1") (pin "A1") (pinfunction "A1_A1") (pintype "bidirectional"))
    )
    (net (code "60") (name "SW3") (class "Default")
      (node (ref "JP2") (pin "3") (pinfunction "3_3") (pintype "passive"))
      (node (ref "U$1") (pin "A2") (pinfunction "A2_A2") (pintype "bidirectional"))
    )
    (net (code "61") (name "SW4") (class "Default")
      (node (ref "JP2") (pin "4") (pinfunction "4_4") (pintype "passive"))
      (node (ref "U$1") (pin "A3") (pinfunction "A3_A3") (pintype "bidirectional"))
    )
    (net (code "62") (name "unconnected-(IC2-I5-Pad5)") (class "Default")
      (node (ref "IC2") (pin "5") (pinfunction "I5_5") (pintype "input"))
    )
    (net (code "63") (name "unconnected-(IC2-I6-Pad6)") (class "Default")
      (node (ref "IC2") (pin "6") (pinfunction "I6_6") (pintype "input"))
    )
    (net (code "64") (name "unconnected-(IC2-I7-Pad7)") (class "Default")
      (node (ref "IC2") (pin "7") (pinfunction "I7_7") (pintype "input"))
    )
    (net (code "65") (name "unconnected-(IC2-O5-Pad12)") (class "Default")
      (node (ref "IC2") (pin "12") (pinfunction "O5_12") (pintype "open_collector"))
    )
    (net (code "66") (name "unconnected-(IC2-O6-Pad11)") (class "Default")
      (node (ref "IC2") (pin "11") (pinfunction "O6_11") (pintype "open_collector"))
    )
    (net (code "67") (name "unconnected-(IC2-O7-Pad10)") (class "Default")
      (node (ref "IC2") (pin "10") (pinfunction "O7_10") (pintype "open_collector"))
    )
    (net (code "68") (name "unconnected-(JP3-Pad4)") (class "Default")
      (node (ref "JP3") (pin "4") (pinfunction "4_4") (pintype "passive"))
    )
    (net (code "69") (name "unconnected-(JP3-Pad5)") (class "Default")
      (node (ref "JP3") (pin "5") (pinfunction "5_5") (pintype "passive"))
    )
    (net (code "70") (name "unconnected-(JP4-Pad4)") (class "Default")
      (node (ref "JP4") (pin "4") (pinfunction "4_4") (pintype "passive"))
    )
    (net (code "71") (name "unconnected-(JP4-Pad5)") (class "Default")
      (node (ref "JP4") (pin "5") (pinfunction "5_5") (pintype "passive"))
    )
    (net (code "72") (name "unconnected-(K1B-O-PadO1)") (class "Default")
      (node (ref "K1") (pin "O1") (pinfunction "O_O1") (pintype "passive"))
    )
    (net (code "73") (name "unconnected-(K1B-P-PadP1)") (class "Default")
      (node (ref "K1") (pin "P1") (pinfunction "P_P1") (pintype "passive"))
    )
    (net (code "74") (name "unconnected-(K1B-S-PadS1)") (class "Default")
      (node (ref "K1") (pin "S1") (pinfunction "S_S1") (pintype "passive"))
    )
    (net (code "75") (name "unconnected-(K1C-O-PadO2)") (class "Default")
      (node (ref "K1") (pin "O2") (pinfunction "O_O2") (pintype "passive"))
    )
    (net (code "76") (name "unconnected-(K1C-P-PadP2)") (class "Default")
      (node (ref "K1") (pin "P2") (pinfunction "P_P2") (pintype "passive"))
    )
    (net (code "77") (name "unconnected-(K1C-S-PadS2)") (class "Default")
      (node (ref "K1") (pin "S2") (pinfunction "S_S2") (pintype "passive"))
    )
    (net (code "78") (name "unconnected-(K2B-O-PadO1)") (class "Default")
      (node (ref "K2") (pin "O1") (pinfunction "O_O1") (pintype "passive"))
    )
    (net (code "79") (name "unconnected-(K2B-P-PadP1)") (class "Default")
      (node (ref "K2") (pin "P1") (pinfunction "P_P1") (pintype "passive"))
    )
    (net (code "80") (name "unconnected-(K2B-S-PadS1)") (class "Default")
      (node (ref "K2") (pin "S1") (pinfunction "S_S1") (pintype "passive"))
    )
    (net (code "81") (name "unconnected-(K2C-O-PadO2)") (class "Default")
      (node (ref "K2") (pin "O2") (pinfunction "O_O2") (pintype "passive"))
    )
    (net (code "82") (name "unconnected-(K2C-P-PadP2)") (class "Default")
      (node (ref "K2") (pin "P2") (pinfunction "P_P2") (pintype "passive"))
    )
    (net (code "83") (name "unconnected-(K2C-S-PadS2)") (class "Default")
      (node (ref "K2") (pin "S2") (pinfunction "S_S2") (pintype "passive"))
    )
    (net (code "84") (name "unconnected-(K3B-O-PadO1)") (class "Default")
      (node (ref "K3") (pin "O1") (pinfunction "O_O1") (pintype "passive"))
    )
    (net (code "85") (name "unconnected-(K3B-P-PadP1)") (class "Default")
      (node (ref "K3") (pin "P1") (pinfunction "P_P1") (pintype "passive"))
    )
    (net (code "86") (name "unconnected-(K3B-S-PadS1)") (class "Default")
      (node (ref "K3") (pin "S1") (pinfunction "S_S1") (pintype "passive"))
    )
    (net (code "87") (name "unconnected-(K3C-O-PadO2)") (class "Default")
      (node (ref "K3") (pin "O2") (pinfunction "O_O2") (pintype "passive"))
    )
    (net (code "88") (name "unconnected-(K3C-P-PadP2)") (class "Default")
      (node (ref "K3") (pin "P2") (pinfunction "P_P2") (pintype "passive"))
    )
    (net (code "89") (name "unconnected-(K3C-S-PadS2)") (class "Default")
      (node (ref "K3") (pin "S2") (pinfunction "S_S2") (pintype "passive"))
    )
    (net (code "90") (name "unconnected-(K4B-O-PadO1)") (class "Default")
      (node (ref "K4") (pin "O1") (pinfunction "O_O1") (pintype "passive"))
    )
    (net (code "91") (name "unconnected-(K4B-P-PadP1)") (class "Default")
      (node (ref "K4") (pin "P1") (pinfunction "P_P1") (pintype "passive"))
    )
    (net (code "92") (name "unconnected-(K4B-S-PadS1)") (class "Default")
      (node (ref "K4") (pin "S1") (pinfunction "S_S1") (pintype "passive"))
    )
    (net (code "93") (name "unconnected-(K4C-O-PadO2)") (class "Default")
      (node (ref "K4") (pin "O2") (pinfunction "O_O2") (pintype "passive"))
    )
    (net (code "94") (name "unconnected-(K4C-P-PadP2)") (class "Default")
      (node (ref "K4") (pin "P2") (pinfunction "P_P2") (pintype "passive"))
    )
    (net (code "95") (name "unconnected-(K4C-S-PadS2)") (class "Default")
      (node (ref "K4") (pin "S2") (pinfunction "S_S2") (pintype "passive"))
    )
    (net (code "96") (name "unconnected-(U$1-Pad3.3V)") (class "Default")
      (node (ref "U$1") (pin "3.3V") (pinfunction "3.3V_3.3V") (pintype "bidirectional"))
    )
    (net (code "97") (name "unconnected-(U$1-PadA4)") (class "Default")
      (node (ref "U$1") (pin "A4") (pinfunction "A4_A4") (pintype "bidirectional"))
    )
    (net (code "98") (name "unconnected-(U$1-PadA5)") (class "Default")
      (node (ref "U$1") (pin "A5") (pinfunction "A5_A5") (pintype "bidirectional"))
    )
    (net (code "99") (name "unconnected-(U$1-PadA6)") (class "Default")
      (node (ref "U$1") (pin "A6") (pinfunction "A6_A6") (pintype "bidirectional"))
    )
    (net (code "100") (name "unconnected-(U$1-PadA7)") (class "Default")
      (node (ref "U$1") (pin "A7") (pinfunction "A7_A7") (pintype "bidirectional"))
    )
    (net (code "101") (name "unconnected-(U$1-PadAREF)") (class "Default")
      (node (ref "U$1") (pin "AREF") (pinfunction "AREF_AREF") (pintype "bidirectional"))
    )
    (net (code "102") (name "unconnected-(U$1-PadD6)") (class "Default")
      (node (ref "U$1") (pin "D6") (pinfunction "D6_D6") (pintype "bidirectional"))
    )
    (net (code "103") (name "unconnected-(U$1-PadICSP1)") (class "Default")
      (node (ref "U$1") (pin "ICSP1") (pinfunction "ICSP1_ICSP1") (pintype "bidirectional"))
    )
    (net (code "104") (name "unconnected-(U$1-PadICSP2)") (class "Default")
      (node (ref "U$1") (pin "ICSP2") (pinfunction "ICSP2_ICSP2") (pintype "bidirectional"))
    )
    (net (code "105") (name "unconnected-(U$1-PadICSP3)") (class "Default")
      (node (ref "U$1") (pin "ICSP3") (pinfunction "ICSP3_ICSP3") (pintype "bidirectional"))
    )
    (net (code "106") (name "unconnected-(U$1-PadICSP4)") (class "Default")
      (node (ref "U$1") (pin "ICSP4") (pinfunction "ICSP4_ICSP4") (pintype "bidirectional"))
    )
    (net (code "107") (name "unconnected-(U$1-PadICSP5)") (class "Default")
      (node (ref "U$1") (pin "ICSP5") (pinfunction "ICSP5_ICSP5") (pintype "bidirectional"))
    )
    (net (code "108") (name "unconnected-(U$1-PadICSP6)") (class "Default")
      (node (ref "U$1") (pin "ICSP6") (pinfunction "ICSP6_ICSP6") (pintype "bidirectional"))
    )
    (net (code "109") (name "unconnected-(U$1-PadRST)") (class "Default")
      (node (ref "U$1") (pin "RST") (pinfunction "RST_RST") (pintype "bidirectional"))
    )
    (net (code "110") (name "unconnected-(U$1-PadRST1)") (class "Default")
      (node (ref "U$1") (pin "RST1") (pinfunction "RST1_RST1") (pintype "bidirectional"))
    )
    (net (code "111") (name "unconnected-(U$1-PadTX0)") (class "Default")
      (node (ref "U$1") (pin "TX0") (pinfunction "TX0_TX0") (pintype "bidirectional"))
    )
  )
)
